# Decoupling_Capacitors.net
KiCad netlist of a schematic drawn in Altium Designer
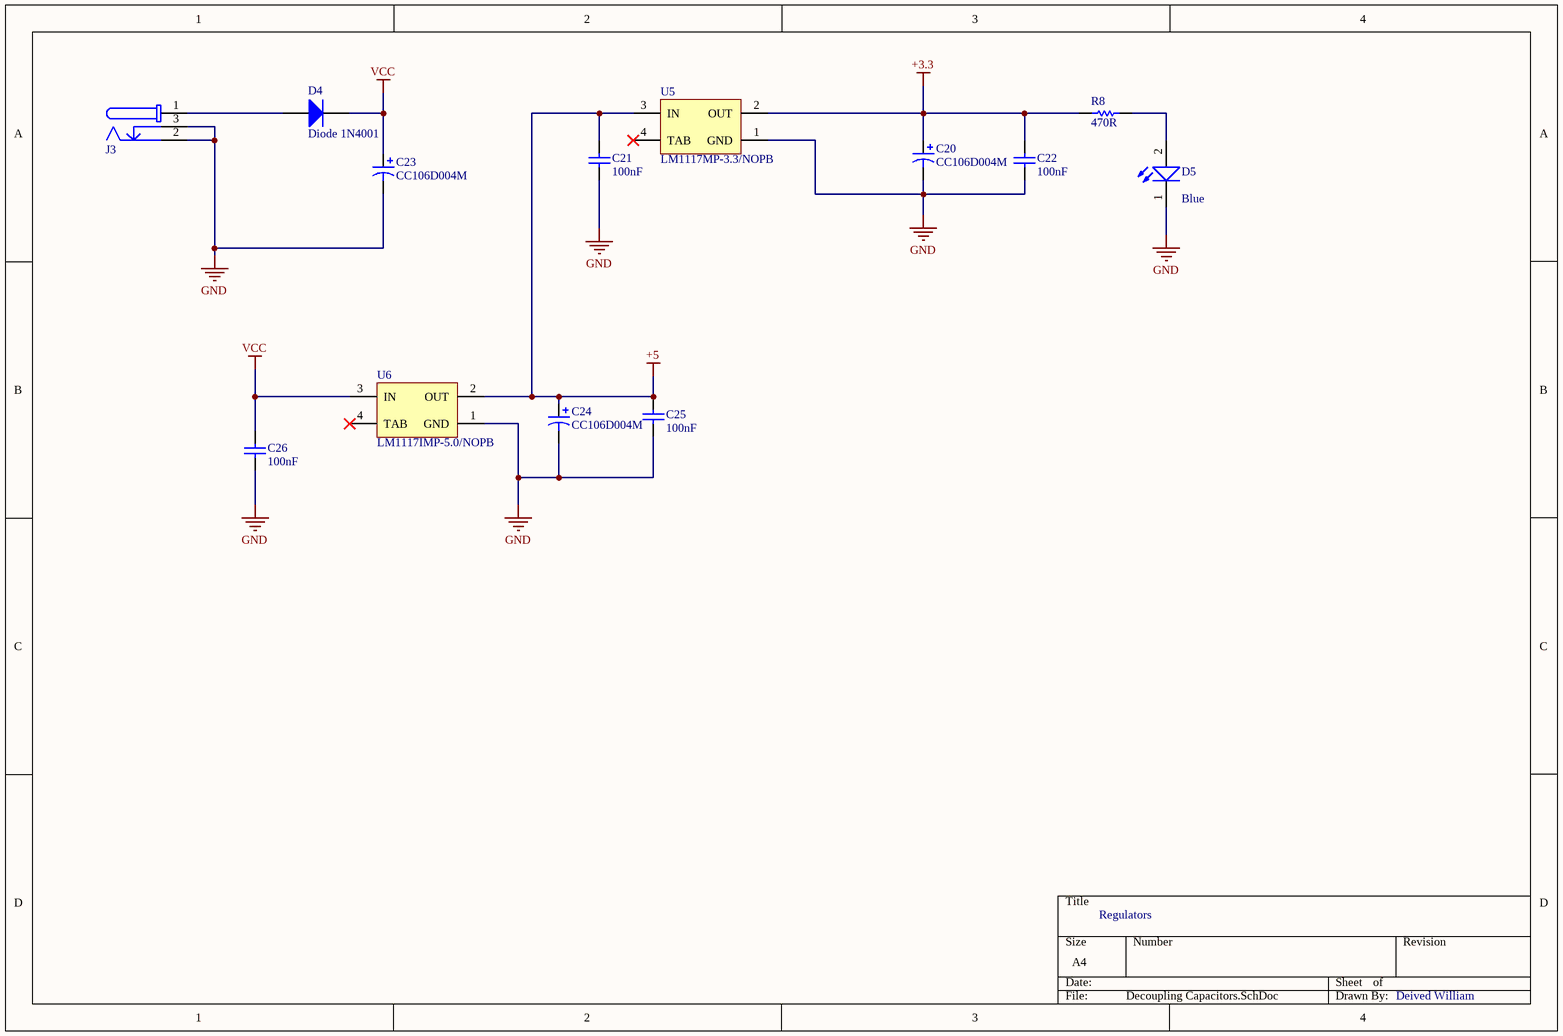
[diagram p0: Decoupling Capacitors.SchDoc]

(export (version "E")
  (design (tool "Eeschema 10.0.6"))
  (components
    (comp (ref "C20")
      (value "CC106D004M")
      (footprint "D")
      (fields (field (name "PUBLISHER") "Altium Limited"))
      (libsource (lib "Vishay Sprague Tantalum Chip Capacitor") (part "CC106D004M"))
    )
    (comp (ref "C21")
      (value "100nF")
      (footprint "WCAP-CSGP_0603, 1.6x0.8x0.8mm_Reflow")
      (description "WCAP-CSGP Ceramic Capacitors, size 0603, 1.6x0.8x0.8mm, 10V, X7R, 100nF")
      (fields (field (name "PART NUMBER") "885012206020") (field (name "PUBLISHER") "Wurth Elektronik"))
      (libsource (lib "Altium_WCAP-CSGP (rev17a)") (part "885012206020"))
    )
    (comp (ref "C22")
      (value "100nF")
      (footprint "WCAP-CSGP_0603, 1.6x0.8x0.8mm_Reflow")
      (description "WCAP-CSGP Ceramic Capacitors, size 0603, 1.6x0.8x0.8mm, 10V, X7R, 100nF")
      (fields (field (name "PART NUMBER") "885012206020") (field (name "PUBLISHER") "Wurth Elektronik"))
      (libsource (lib "Altium_WCAP-CSGP (rev17a)") (part "885012206020"))
    )
    (comp (ref "C23")
      (value "CC106D004M")
      (footprint "D")
      (fields (field (name "PUBLISHER") "Altium Limited"))
      (libsource (lib "Vishay Sprague Tantalum Chip Capacitor") (part "CC106D004M"))
    )
    (comp (ref "C24")
      (value "CC106D004M")
      (footprint "D")
      (fields (field (name "PUBLISHER") "Altium Limited"))
      (libsource (lib "Vishay Sprague Tantalum Chip Capacitor") (part "CC106D004M"))
    )
    (comp (ref "C25")
      (value "100nF")
      (footprint "WCAP-CSGP_0603, 1.6x0.8x0.8mm_Reflow")
      (description "WCAP-CSGP Ceramic Capacitors, size 0603, 1.6x0.8x0.8mm, 10V, X7R, 100nF")
      (fields (field (name "PART NUMBER") "885012206020") (field (name "PUBLISHER") "Wurth Elektronik"))
      (libsource (lib "Altium_WCAP-CSGP (rev17a)") (part "885012206020"))
    )
    (comp (ref "C26")
      (value "100nF")
      (footprint "WCAP-CSGP_0603, 1.6x0.8x0.8mm_Reflow")
      (description "WCAP-CSGP Ceramic Capacitors, size 0603, 1.6x0.8x0.8mm, 10V, X7R, 100nF")
      (fields (field (name "PART NUMBER") "885012206020") (field (name "PUBLISHER") "Wurth Elektronik"))
      (libsource (lib "Altium_WCAP-CSGP (rev17a)") (part "885012206020"))
    )
    (comp (ref "D4")
      (value "Diode 1N4001")
      (footprint "DO-41")
      (description "1 Amp General Purpose Rectifier")
      (fields (field (name "PUBLISHER") "Altium Limited"))
      (libsource (lib "Miscellaneous Devices") (part "Diode 1N4001"))
    )
    (comp (ref "D5")
      (value "150080BS75000")
      (footprint "WL-SMCW_0805")
      (description "WL-SMCW SMD Mono-color Chip LED Waterclear, size 0805, Blue")
      (fields (field (name "EMITTING COLOR") "Blue") (field (name "PUBLISHER") "Wurth Elektronik"))
      (libsource (lib "ALTIUM-WL-SMCW-rev17a") (part "150080BS75000"))
    )
    (comp (ref "J3")
      (value "694108301002")
      (footprint "694108301002")
      (description "DC Power Jack Right Angled(6.4) WR-DC")
      (fields (field (name "PUBLISHER") "Wurth Elektronik"))
      (libsource (lib "Altium_WR-DC_POWER_JACK_CONNECTORS (rev17a)") (part "694108301002"))
    )
    (comp (ref "R8")
      (value "470R")
      (footprint "3-0603")
      (fields (field (name "PUBLISHER") "Altium Limited"))
      (libsource (lib "Panasonic Resistor") (part "ERJ3RE"))
    )
    (comp (ref "U5")
      (value "LM1117MP-3.3/NOPB")
      (footprint "MP04A_N")
      (description "800mA Low-Dropout Linear Regulator, 4-pin SOT-223, Pb-Free")
      (fields
        (field (name "MANUFACTURER") "National Semiconductor")
        (field (name "PUBLISHER") "Altium Limited")
      )
      (libsource (lib "NSC LDO") (part "LM1117MP-3.3/NOPB"))
    )
    (comp (ref "U6")
      (value "LM1117IMP-5.0/NOPB")
      (footprint "MP04A_N")
      (description "800mA Low-Dropout Linear Regulator, 4-pin SOT-223, Pb-Free")
      (fields
        (field (name "MANUFACTURER") "National Semiconductor")
        (field (name "PUBLISHER") "Altium Limited")
      )
      (libsource (lib "NSC LDO") (part "LM1117IMP-5.0/NOPB"))
    )
  )
  (nets
    (net (code "1") (name "+3.3") (class "Default")
      (node (ref "C20") (pin "1") (pinfunction "1_1") (pintype "passive"))
      (node (ref "C22") (pin "2") (pinfunction "2_2") (pintype "passive"))
      (node (ref "R8") (pin "1") (pinfunction "1_1") (pintype "passive"))
      (node (ref "U5") (pin "2") (pinfunction "OUT_2") (pintype "power_in"))
    )
    (net (code "2") (name "+5") (class "Default")
      (node (ref "C21") (pin "2") (pinfunction "2_2") (pintype "passive"))
      (node (ref "C24") (pin "1") (pinfunction "1_1") (pintype "passive"))
      (node (ref "C25") (pin "2") (pinfunction "2_2") (pintype "passive"))
      (node (ref "U5") (pin "3") (pinfunction "IN_3") (pintype "power_in"))
      (node (ref "U6") (pin "2") (pinfunction "OUT_2") (pintype "power_in"))
    )
    (net (code "3") (name "GND") (class "Default")
      (node (ref "C20") (pin "2") (pinfunction "2_2") (pintype "passive"))
      (node (ref "C21") (pin "1") (pinfunction "1_1") (pintype "passive"))
      (node (ref "C22") (pin "1") (pinfunction "1_1") (pintype "passive"))
      (node (ref "C23") (pin "2") (pinfunction "2_2") (pintype "passive"))
      (node (ref "C24") (pin "2") (pinfunction "2_2") (pintype "passive"))
      (node (ref "C25") (pin "1") (pinfunction "1_1") (pintype "passive"))
      (node (ref "C26") (pin "1") (pinfunction "1_1") (pintype "passive"))
      (node (ref "D5") (pin "1") (pinfunction "K_1") (pintype "passive"))
      (node (ref "J3") (pin "2") (pinfunction "2_2") (pintype "passive"))
      (node (ref "J3") (pin "3") (pinfunction "3_3") (pintype "passive"))
      (node (ref "U5") (pin "1") (pinfunction "GND_1") (pintype "power_in"))
      (node (ref "U6") (pin "1") (pinfunction "GND_1") (pintype "power_in"))
    )
    (net (code "4") (name "Net-(D4-A)") (class "Default")
      (node (ref "D4") (pin "1") (pinfunction "A_1") (pintype "passive"))
      (node (ref "J3") (pin "1") (pinfunction "1_1") (pintype "passive"))
    )
    (net (code "5") (name "Net-(D5-A)") (class "Default")
      (node (ref "D5") (pin "2") (pinfunction "A_2") (pintype "passive"))
      (node (ref "R8") (pin "2") (pinfunction "2_2") (pintype "passive"))
    )
    (net (code "6") (name "VCC") (class "Default")
      (node (ref "C23") (pin "1") (pinfunction "1_1") (pintype "passive"))
      (node (ref "C26") (pin "2") (pinfunction "2_2") (pintype "passive"))
      (node (ref "D4") (pin "2") (pinfunction "K_2") (pintype "passive"))
      (node (ref "U6") (pin "3") (pinfunction "IN_3") (pintype "power_in"))
    )
    (net (code "7") (name "unconnected-(U5-TAB-Pad4)") (class "Default")
      (node (ref "U5") (pin "4") (pinfunction "TAB_4") (pintype "power_in+no_connect"))
    )
    (net (code "8") (name "unconnected-(U6-TAB-Pad4)") (class "Default")
      (node (ref "U6") (pin "4") (pinfunction "TAB_4") (pintype "power_in+no_connect"))
    )
  )
)
